# Qwiic_Accelerometer_LIS2DH12.net
KiCad netlist of a schematic drawn in EAGLE
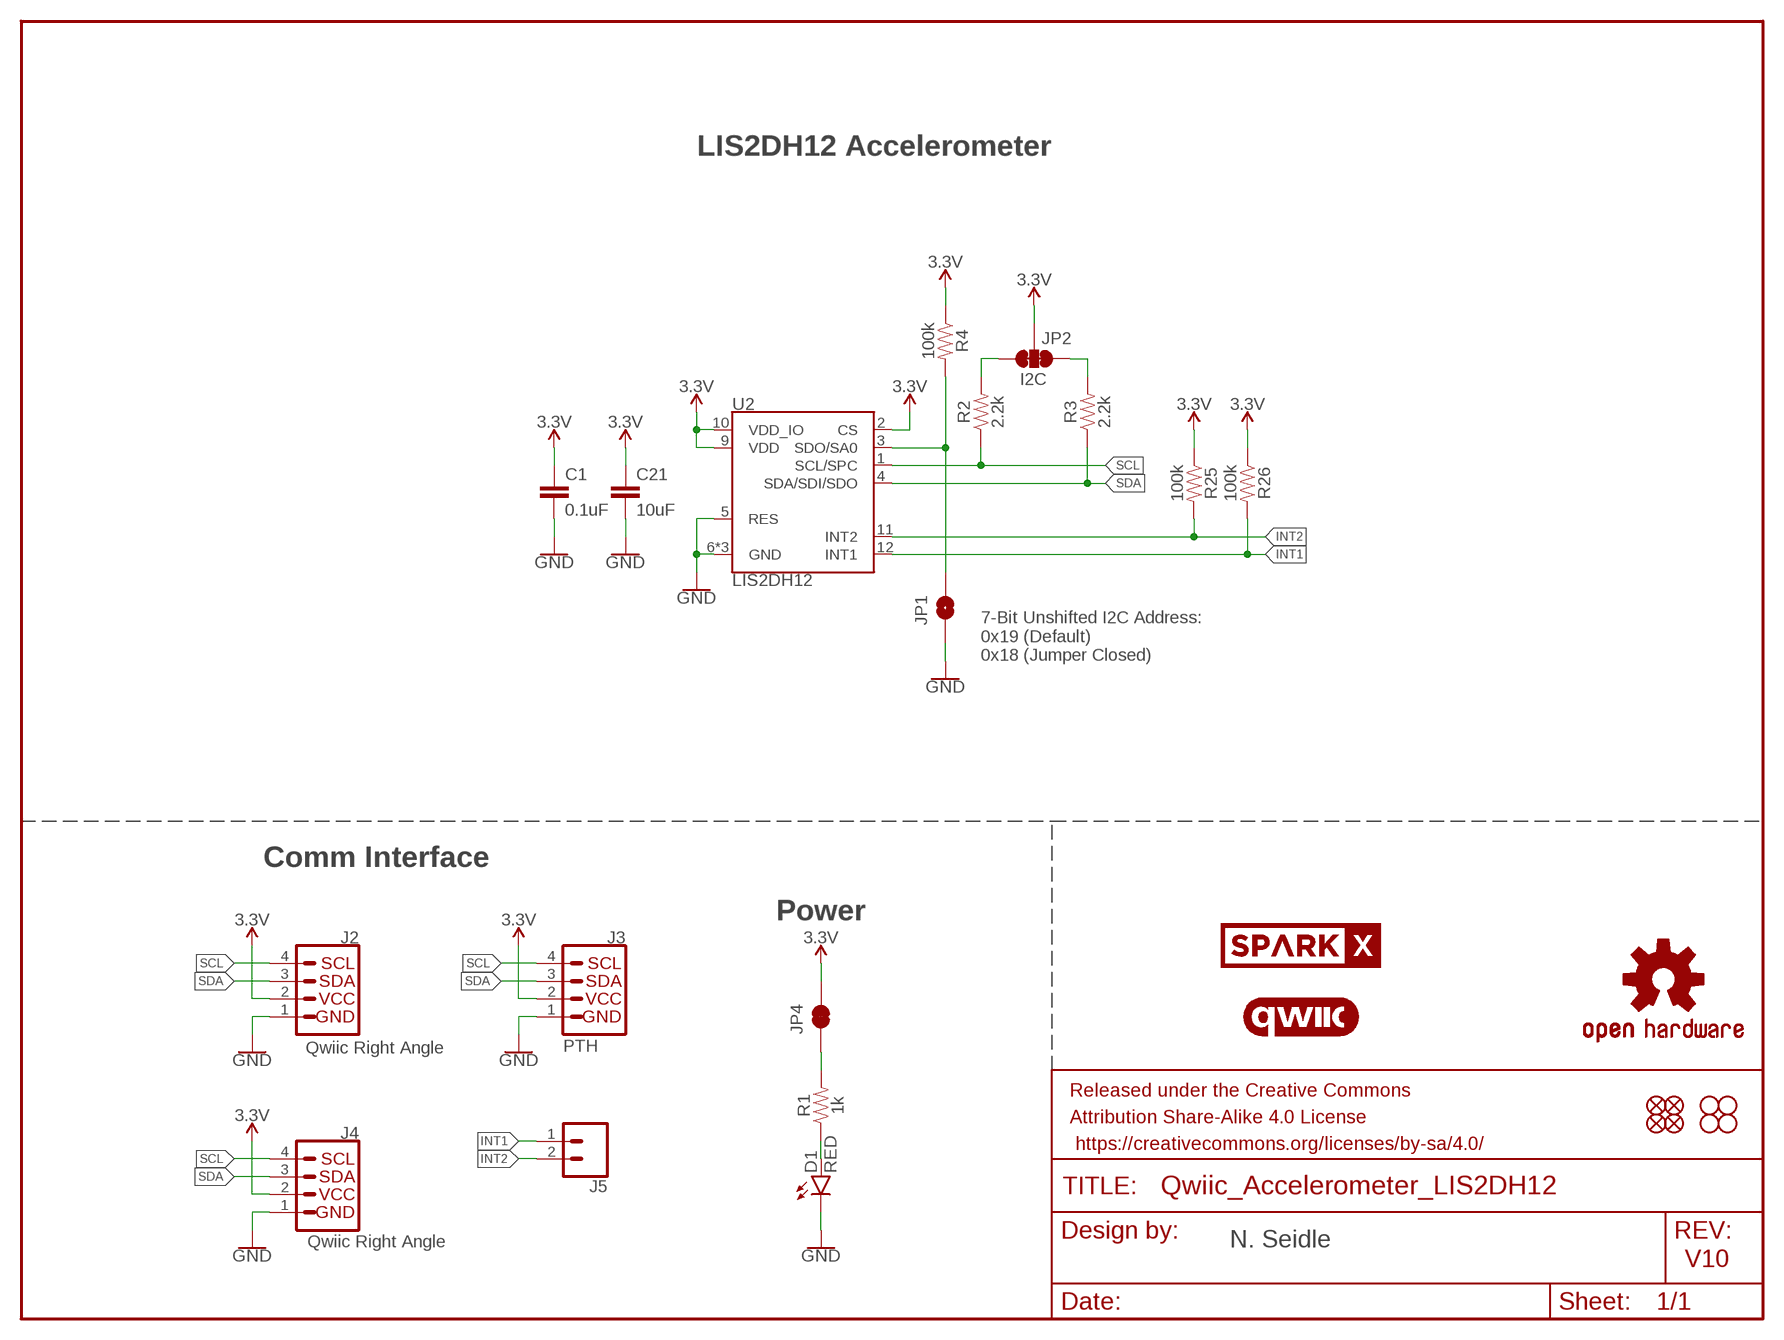
[diagram p0: schematic, sheet 1]

(export (version "E")
  (design (tool "Eeschema 10.0.6"))
  (components
    (comp (ref "C1")
      (value "0.1uF")
      (footprint "eagle-import:0603")
      (libsource (lib "eagle-import") (part "0.1UF-0603-25V-(+80/-20%)"))
    )
    (comp (ref "C21")
      (value "10uF")
      (footprint "eagle-import:0603")
      (libsource (lib "eagle-import") (part "10UF-0603-6.3V-20%"))
    )
    (comp (ref "D1")
      (value "RED")
      (footprint "eagle-import:LED-0603")
      (libsource (lib "eagle-import") (part "LED-RED0603"))
    )
    (comp (ref "FD1")
      (value "FIDUCIALUFIDUCIAL")
      (footprint "eagle-import:FIDUCIAL-MICRO")
      (libsource (lib "eagle-import") (part "FIDUCIALUFIDUCIAL"))
    )
    (comp (ref "FD2")
      (value "FIDUCIALUFIDUCIAL")
      (footprint "eagle-import:FIDUCIAL-MICRO")
      (libsource (lib "eagle-import") (part "FIDUCIALUFIDUCIAL"))
    )
    (comp (ref "FD3")
      (value "FIDUCIALUFIDUCIAL")
      (footprint "eagle-import:FIDUCIAL-MICRO")
      (libsource (lib "eagle-import") (part "FIDUCIALUFIDUCIAL"))
    )
    (comp (ref "FD4")
      (value "FIDUCIALUFIDUCIAL")
      (footprint "eagle-import:FIDUCIAL-MICRO")
      (libsource (lib "eagle-import") (part "FIDUCIALUFIDUCIAL"))
    )
    (comp (ref "FRAME1")
      (value "FRAME-LETTER")
      (footprint "eagle-import:CREATIVE_COMMONS")
      (libsource (lib "eagle-import") (part "FRAME-LETTER"))
    )
    (comp (ref "H1")
      (value "STAND-OFF")
      (footprint "eagle-import:STAND-OFF")
      (libsource (lib "eagle-import") (part "STAND-OFF"))
    )
    (comp (ref "H2")
      (value "STAND-OFF")
      (footprint "eagle-import:STAND-OFF")
      (libsource (lib "eagle-import") (part "STAND-OFF"))
    )
    (comp (ref "H3")
      (value "STAND-OFF")
      (footprint "eagle-import:STAND-OFF")
      (libsource (lib "eagle-import") (part "STAND-OFF"))
    )
    (comp (ref "H4")
      (value "STAND-OFF")
      (footprint "eagle-import:STAND-OFF")
      (libsource (lib "eagle-import") (part "STAND-OFF"))
    )
    (comp (ref "J2")
      (value "Qwiic Right Angle")
      (footprint "eagle-import:JST04_1MM_RA")
      (libsource (lib "eagle-import") (part "I2C_STANDARDQWIIC"))
    )
    (comp (ref "J3")
      (value "PTH")
      (footprint "eagle-import:1X04_NO_SILK")
      (libsource (lib "eagle-import") (part "I2C_STANDARD_NO_SILK"))
    )
    (comp (ref "J4")
      (value "Qwiic Right Angle")
      (footprint "eagle-import:JST04_1MM_RA")
      (libsource (lib "eagle-import") (part "I2C_STANDARDQWIIC"))
    )
    (comp (ref "J5")
      (value "CONN_021X02_NO_SILK")
      (footprint "eagle-import:1X02_NO_SILK")
      (libsource (lib "eagle-import") (part "CONN_021X02_NO_SILK"))
    )
    (comp (ref "JP1")
      (value "JUMPER-SMT_2_NO_SILK")
      (footprint "eagle-import:SMT-JUMPER_2_NO_SILK")
      (libsource (lib "eagle-import") (part "JUMPER-SMT_2_NO_SILK"))
    )
    (comp (ref "JP2")
      (value "I2C")
      (footprint "eagle-import:SMT-JUMPER_3_2-NC_TRACE_SILK")
      (libsource (lib "eagle-import") (part "JUMPER-SMT_3_2-NC_TRACE_SILK"))
    )
    (comp (ref "JP4")
      (value "JUMPER-SMT_2_NC_TRACE_SILK")
      (footprint "eagle-import:SMT-JUMPER_2_NC_TRACE_SILK")
      (libsource (lib "eagle-import") (part "JUMPER-SMT_2_NC_TRACE_SILK"))
    )
    (comp (ref "LOGO1")
      (value "OSHW-LOGOMINI")
      (footprint "eagle-import:OSHW-LOGO-MINI")
      (libsource (lib "eagle-import") (part "OSHW-LOGOMINI"))
    )
    (comp (ref "LOGO4")
      (value "QWIIC_LOGO_CONNECTOR")
      (footprint "eagle-import:QWIIC_5.5MM")
      (libsource (lib "eagle-import") (part "QWIIC_LOGO_CONNECTOR"))
    )
    (comp (ref "R1")
      (value "1k")
      (footprint "eagle-import:0603")
      (libsource (lib "eagle-import") (part "1KOHM-0603-1/10W-1%"))
    )
    (comp (ref "R2")
      (value "2.2k")
      (footprint "eagle-import:0603")
      (libsource (lib "eagle-import") (part "2.2KOHM-0603-1/10W-1%"))
    )
    (comp (ref "R3")
      (value "2.2k")
      (footprint "eagle-import:0603")
      (libsource (lib "eagle-import") (part "2.2KOHM-0603-1/10W-1%"))
    )
    (comp (ref "R4")
      (value "100k")
      (footprint "eagle-import:0603")
      (libsource (lib "eagle-import") (part "100KOHM-0603-1/10W-1%"))
    )
    (comp (ref "R25")
      (value "100k")
      (footprint "eagle-import:0603")
      (libsource (lib "eagle-import") (part "100KOHM-0603-1/10W-1%"))
    )
    (comp (ref "R26")
      (value "100k")
      (footprint "eagle-import:0603")
      (libsource (lib "eagle-import") (part "100KOHM-0603-1/10W-1%"))
    )
    (comp (ref "U$30")
      (value "SPARKX-LOGO4")
      (footprint "eagle-import:SPARKX-MEDIUM")
      (libsource (lib "eagle-import") (part "SPARKX-LOGO4"))
    )
    (comp (ref "U2")
      (value "LIS2DH12")
      (footprint "eagle-import:LGA-12-LISDH12")
      (libsource (lib "eagle-import") (part "LIS2DH12"))
    )
  )
  (nets
    (net (code "1") (name "3.3V") (class "Default")
      (node (ref "C1") (pin "1") (pinfunction "1_1") (pintype "passive"))
      (node (ref "C21") (pin "1") (pinfunction "1_1") (pintype "passive"))
      (node (ref "J2") (pin "2") (pinfunction "2_2") (pintype "power_in"))
      (node (ref "J3") (pin "2") (pinfunction "2_2") (pintype "power_in"))
      (node (ref "J4") (pin "2") (pinfunction "2_2") (pintype "power_in"))
      (node (ref "JP2") (pin "2") (pinfunction "2_2") (pintype "passive"))
      (node (ref "JP4") (pin "2") (pinfunction "2_2") (pintype "passive"))
      (node (ref "R25") (pin "1") (pinfunction "1_1") (pintype "passive"))
      (node (ref "R26") (pin "1") (pinfunction "1_1") (pintype "passive"))
      (node (ref "R4") (pin "1") (pinfunction "1_1") (pintype "passive"))
      (node (ref "U2") (pin "10") (pinfunction "VDD_IO_10") (pintype "bidirectional"))
      (node (ref "U2") (pin "2") (pinfunction "CS_2") (pintype "bidirectional"))
      (node (ref "U2") (pin "9") (pinfunction "VDD_9") (pintype "bidirectional"))
    )
    (net (code "2") (name "GND") (class "Default")
      (node (ref "C1") (pin "2") (pinfunction "2_2") (pintype "passive"))
      (node (ref "C21") (pin "2") (pinfunction "2_2") (pintype "passive"))
      (node (ref "D1") (pin "C") (pinfunction "C_C") (pintype "passive"))
      (node (ref "J2") (pin "1") (pinfunction "1_1") (pintype "power_in"))
      (node (ref "J3") (pin "1") (pinfunction "1_1") (pintype "power_in"))
      (node (ref "J4") (pin "1") (pinfunction "1_1") (pintype "power_in"))
      (node (ref "JP1") (pin "1") (pinfunction "1_1") (pintype "passive"))
      (node (ref "U2") (pin "5") (pinfunction "RES_5") (pintype "bidirectional"))
      (node (ref "U2") (pin "6") (pinfunction "GND_6") (pintype "bidirectional"))
      (node (ref "U2") (pin "7") (pinfunction "GND_7") (pintype "bidirectional"))
      (node (ref "U2") (pin "8") (pinfunction "GND_8") (pintype "bidirectional"))
    )
    (net (code "3") (name "INT1") (class "Default")
      (node (ref "J5") (pin "1") (pinfunction "1_1") (pintype "passive"))
      (node (ref "R26") (pin "2") (pinfunction "2_2") (pintype "passive"))
      (node (ref "U2") (pin "12") (pinfunction "INT1_12") (pintype "bidirectional"))
    )
    (net (code "4") (name "INT2") (class "Default")
      (node (ref "J5") (pin "2") (pinfunction "2_2") (pintype "passive"))
      (node (ref "R25") (pin "2") (pinfunction "2_2") (pintype "passive"))
      (node (ref "U2") (pin "11") (pinfunction "INT2_11") (pintype "bidirectional"))
    )
    (net (code "5") (name "Net-(D1-PadA)") (class "Default")
      (node (ref "D1") (pin "A") (pinfunction "A_A") (pintype "passive"))
      (node (ref "R1") (pin "1") (pinfunction "1_1") (pintype "passive"))
    )
    (net (code "6") (name "Net-(JP2-Pad1)") (class "Default")
      (node (ref "JP2") (pin "1") (pinfunction "1_1") (pintype "passive"))
      (node (ref "R3") (pin "2") (pinfunction "2_2") (pintype "passive"))
    )
    (net (code "7") (name "Net-(JP2-Pad3)") (class "Default")
      (node (ref "JP2") (pin "3") (pinfunction "3_3") (pintype "passive"))
      (node (ref "R2") (pin "2") (pinfunction "2_2") (pintype "passive"))
    )
    (net (code "8") (name "Net-(JP4-Pad1)") (class "Default")
      (node (ref "JP4") (pin "1") (pinfunction "1_1") (pintype "passive"))
      (node (ref "R1") (pin "2") (pinfunction "2_2") (pintype "passive"))
    )
    (net (code "9") (name "Net-(U2-SDO{slash}SA0)") (class "Default")
      (node (ref "JP1") (pin "2") (pinfunction "2_2") (pintype "passive"))
      (node (ref "R4") (pin "2") (pinfunction "2_2") (pintype "passive"))
      (node (ref "U2") (pin "3") (pinfunction "SDO/SA0_3") (pintype "bidirectional"))
    )
    (net (code "10") (name "SCL") (class "Default")
      (node (ref "J2") (pin "4") (pinfunction "4_4") (pintype "passive"))
      (node (ref "J3") (pin "4") (pinfunction "4_4") (pintype "passive"))
      (node (ref "J4") (pin "4") (pinfunction "4_4") (pintype "passive"))
      (node (ref "R2") (pin "1") (pinfunction "1_1") (pintype "passive"))
      (node (ref "U2") (pin "1") (pinfunction "SCL/SPC_1") (pintype "bidirectional"))
    )
    (net (code "11") (name "SDA") (class "Default")
      (node (ref "J2") (pin "3") (pinfunction "3_3") (pintype "passive"))
      (node (ref "J3") (pin "3") (pinfunction "3_3") (pintype "passive"))
      (node (ref "J4") (pin "3") (pinfunction "3_3") (pintype "passive"))
      (node (ref "R3") (pin "1") (pinfunction "1_1") (pintype "passive"))
      (node (ref "U2") (pin "4") (pinfunction "SDA/SDI/SDO_4") (pintype "bidirectional"))
    )
  )
)
